# powerbank.net
KiCad netlist of a schematic drawn in EasyEDA Pro
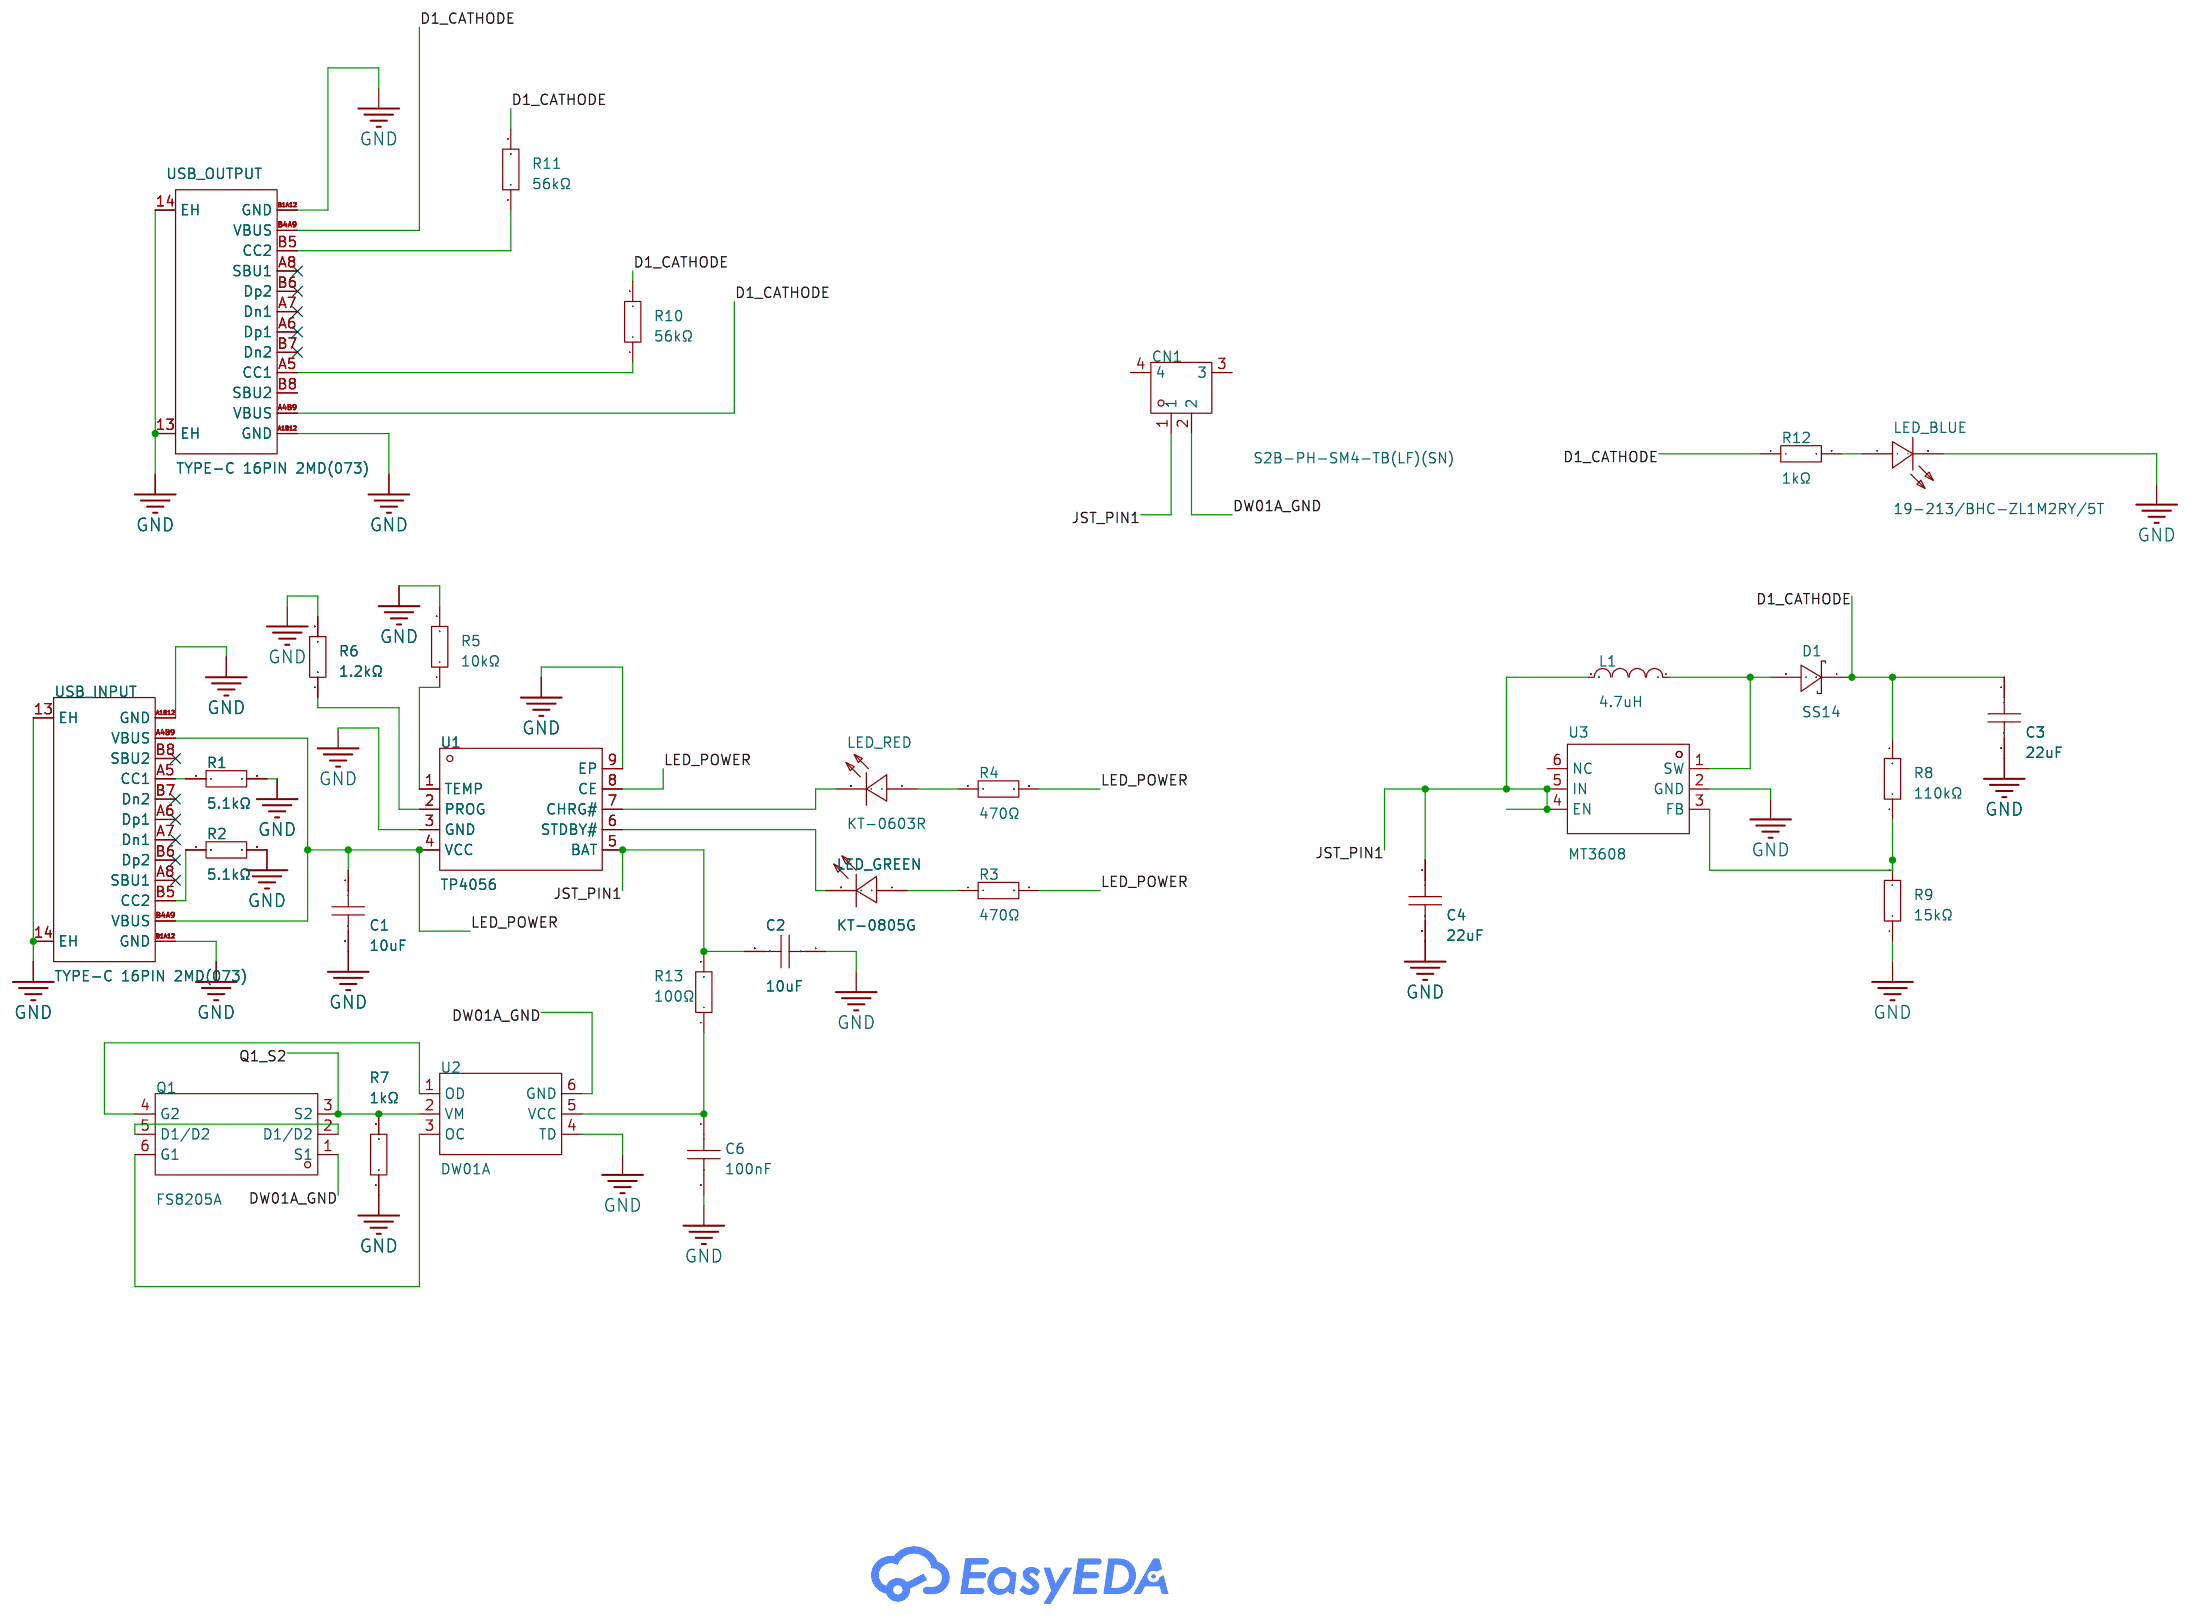
[diagram p0: schematic sheet]

(export (version "E")
  (design (tool "Eeschema 10.0.6"))
  (components
    (comp (ref "C1")
      (value "10uF")
      (footprint "easyedapro:C0201")
      (libsource (lib "easyedapro") (part "CAP"))
    )
    (comp (ref "C2")
      (value "10uF")
      (footprint "easyedapro:C0201")
      (libsource (lib "easyedapro") (part "CAP"))
    )
    (comp (ref "C3")
      (value "22uF")
      (footprint "easyedapro:C0201")
      (libsource (lib "easyedapro") (part "CAP"))
    )
    (comp (ref "C4")
      (value "22uF")
      (footprint "easyedapro:C0201")
      (libsource (lib "easyedapro") (part "CAP"))
    )
    (comp (ref "C6")
      (value "100nF")
      (footprint "easyedapro:C0201")
      (libsource (lib "easyedapro") (part "CAP"))
    )
    (comp (ref "CN1")
      (value "S2B-PH-SM4-TB(LF)(SN)")
      (footprint "easyedapro:CONN-SMD_P2.00_S2B-PH-SM4-TB-LF-SN")
      (fields (field (name "Manufacturer") "JST"))
      (libsource (lib "easyedapro") (part "S2B-PH-SM4-TB(LF)(SN)"))
    )
    (comp (ref "D1")
      (value "SS14")
      (footprint "easyedapro:SMA_L4.2-W2.6-LS5.3-RD")
      (fields (field (name "Manufacturer") "LJ(朗捷)"))
      (libsource (lib "easyedapro") (part "SS14_C7450452"))
    )
    (comp (ref "L1")
      (value "4.7uH")
      (footprint "easyedapro:IND-SMD_L4.4-W4.2")
      (fields (field (name "Manufacturer Part") "FXL0420-4R7-M") (field (name "Manufacturer") "cjiang(长江微电)"))
      (libsource (lib "easyedapro") (part "FXL0420-4R7-M"))
    )
    (comp (ref "LED_BLUE")
      (value "19-213/BHC-ZL1M2RY/5T")
      (footprint "easyedapro:LED0603-R-RD_BLUE")
      (fields (field (name "Manufacturer") "EVERLIGHT(亿光)"))
      (libsource (lib "easyedapro") (part "19-213/BHC-ZL1M2RY/5T"))
    )
    (comp (ref "LED_GREEN")
      (value "KT-0805G")
      (footprint "easyedapro:LED0805-R-RD")
      (fields (field (name "Manufacturer") "KENTO"))
      (libsource (lib "easyedapro") (part "0805G (Green)"))
    )
    (comp (ref "LED_RED")
      (value "KT-0603R")
      (footprint "easyedapro:LED-SMD_L1.6-W0.8-R-RD")
      (fields (field (name "Manufacturer") "KENTO"))
      (libsource (lib "easyedapro") (part "KT-0603R"))
    )
    (comp (ref "Q1")
      (value "FS8205A")
      (footprint "easyedapro:SOT-23-6_L2.9-W1.6-P0.95-LS2.8-BR")
      (fields (field (name "Manufacturer") "TECH PUBLIC(台舟)"))
      (libsource (lib "easyedapro") (part "FS8205A_C2830320"))
    )
    (comp (ref "R1")
      (value "5.1kΩ")
      (footprint "easyedapro:R0603")
      (libsource (lib "easyedapro") (part "Res"))
    )
    (comp (ref "R2")
      (value "5.1kΩ")
      (footprint "easyedapro:R0603")
      (libsource (lib "easyedapro") (part "Res"))
    )
    (comp (ref "R3")
      (value "470Ω")
      (footprint "easyedapro:R0603")
      (libsource (lib "easyedapro") (part "Res"))
    )
    (comp (ref "R4")
      (value "470Ω")
      (footprint "easyedapro:R0603")
      (libsource (lib "easyedapro") (part "Res"))
    )
    (comp (ref "R5")
      (value "10kΩ")
      (footprint "easyedapro:R0603")
      (libsource (lib "easyedapro") (part "Res"))
    )
    (comp (ref "R6")
      (value "1.2kΩ")
      (footprint "easyedapro:R0603")
      (libsource (lib "easyedapro") (part "Res"))
    )
    (comp (ref "R7") (value "1kΩ") (footprint "easyedapro:R0603") (libsource (lib "easyedapro") (part "Res")))
    (comp (ref "R8")
      (value "110kΩ")
      (footprint "easyedapro:R0603")
      (libsource (lib "easyedapro") (part "Res"))
    )
    (comp (ref "R9")
      (value "15kΩ")
      (footprint "easyedapro:R0603")
      (libsource (lib "easyedapro") (part "Res"))
    )
    (comp (ref "R10")
      (value "56kΩ")
      (footprint "easyedapro:R0603")
      (libsource (lib "easyedapro") (part "Res"))
    )
    (comp (ref "R11")
      (value "56kΩ")
      (footprint "easyedapro:R0603")
      (libsource (lib "easyedapro") (part "Res"))
    )
    (comp (ref "R12")
      (value "1kΩ")
      (footprint "easyedapro:R0603")
      (libsource (lib "easyedapro") (part "Res"))
    )
    (comp (ref "R13")
      (value "100Ω")
      (footprint "easyedapro:R0603")
      (libsource (lib "easyedapro") (part "Res"))
    )
    (comp (ref "U1")
      (value "TP4056")
      (footprint "easyedapro:ESOP-8_L4.9-W3.9-P1.27-LS6.0-BL-EP")
      (fields (field (name "Manufacturer") "TPOWER(天源)"))
      (libsource (lib "easyedapro") (part "TP4056_C382139"))
    )
    (comp (ref "U2")
      (value "DW01A")
      (footprint "easyedapro:SOT-23-6_L2.9-W1.6-P0.95-LS2.8-BL")
      (fields (field (name "Manufacturer") "PUOLOP(迪浦)"))
      (libsource (lib "easyedapro") (part "DW01A_C351410"))
    )
    (comp (ref "U3")
      (value "MT3608")
      (footprint "easyedapro:SOT-23-6_L2.9-W1.6-P0.95-LS2.8-BL")
      (fields (field (name "Manufacturer") "西安航天民芯"))
      (libsource (lib "easyedapro") (part "MT3608"))
    )
    (comp (ref "USB_INPUT")
      (value "TYPE-C 16PIN 2MD(073)")
      (footprint "easyedapro:USB-C-SMD_TYPE-C-16PIN-2MD-073")
      (fields (field (name "Manufacturer") "SHOU HAN(首韩)"))
      (libsource (lib "easyedapro") (part "TYPE-C 16PIN 2MD(073)"))
    )
    (comp (ref "USB_OUTPUT")
      (value "TYPE-C 16PIN 2MD(073)")
      (footprint "easyedapro:USB-C-SMD_TYPE-C-16PIN-2MD-073")
      (fields (field (name "Manufacturer") "SHOU HAN(首韩)"))
      (libsource (lib "easyedapro") (part "TYPE-C 16PIN 2MD(073)"))
    )
  )
  (nets
    (net (code "1") (name "/D1_CATHODE") (class "Default")
      (node (ref "C3") (pin "1") (pinfunction "1_1") (pintype "input"))
      (node (ref "D1") (pin "1") (pinfunction "C_1") (pintype "unspecified"))
      (node (ref "R10") (pin "2") (pinfunction "2_2") (pintype "input"))
      (node (ref "R11") (pin "2") (pinfunction "2_2") (pintype "input"))
      (node (ref "R12") (pin "1") (pinfunction "1_1") (pintype "input"))
      (node (ref "R8") (pin "2") (pinfunction "2_2") (pintype "input"))
      (node (ref "USB_OUTPUT") (pin "A4B9") (pinfunction "VBUS_A4B9") (pintype "unspecified"))
      (node (ref "USB_OUTPUT") (pin "B4A9") (pinfunction "VBUS_B4A9") (pintype "unspecified"))
    )
    (net (code "2") (name "/DW01A_GND") (class "Default")
      (node (ref "CN1") (pin "2") (pinfunction "2_2") (pintype "unspecified"))
      (node (ref "Q1") (pin "1") (pinfunction "S1_1") (pintype "unspecified"))
      (node (ref "U2") (pin "6") (pinfunction "GND_6") (pintype "unspecified"))
    )
    (net (code "3") (name "/JST_PIN1") (class "Default")
      (node (ref "C2") (pin "2") (pinfunction "2_2") (pintype "input"))
      (node (ref "C4") (pin "1") (pinfunction "1_1") (pintype "input"))
      (node (ref "CN1") (pin "1") (pinfunction "1_1") (pintype "unspecified"))
      (node (ref "L1") (pin "2") (pinfunction "2_2") (pintype "unspecified"))
      (node (ref "R13") (pin "2") (pinfunction "2_2") (pintype "input"))
      (node (ref "U1") (pin "5") (pinfunction "BAT_5") (pintype "unspecified"))
      (node (ref "U3") (pin "4") (pinfunction "EN_4") (pintype "unspecified"))
      (node (ref "U3") (pin "5") (pinfunction "IN_5") (pintype "unspecified"))
    )
    (net (code "4") (name "/LED_POWER") (class "Default")
      (node (ref "C1") (pin "1") (pinfunction "1_1") (pintype "input"))
      (node (ref "R3") (pin "2") (pinfunction "2_2") (pintype "input"))
      (node (ref "R4") (pin "2") (pinfunction "2_2") (pintype "input"))
      (node (ref "U1") (pin "4") (pinfunction "VCC_4") (pintype "unspecified"))
      (node (ref "U1") (pin "8") (pinfunction "CE_8") (pintype "unspecified"))
      (node (ref "USB_INPUT") (pin "A4B9") (pinfunction "VBUS_A4B9") (pintype "unspecified"))
      (node (ref "USB_INPUT") (pin "B4A9") (pinfunction "VBUS_B4A9") (pintype "unspecified"))
    )
    (net (code "5") (name "/Q1_S2") (class "Default")
      (node (ref "Q1") (pin "3") (pinfunction "S2_3") (pintype "unspecified"))
      (node (ref "R7") (pin "2") (pinfunction "2_2") (pintype "input"))
      (node (ref "U2") (pin "2") (pinfunction "VM_2") (pintype "unspecified"))
    )
    (net (code "6") (name "GND") (class "Default")
      (node (ref "C1") (pin "2") (pinfunction "2_2") (pintype "input"))
      (node (ref "C2") (pin "1") (pinfunction "1_1") (pintype "input"))
      (node (ref "C3") (pin "2") (pinfunction "2_2") (pintype "input"))
      (node (ref "C4") (pin "2") (pinfunction "2_2") (pintype "input"))
      (node (ref "C6") (pin "2") (pinfunction "2_2") (pintype "input"))
      (node (ref "LED_BLUE") (pin "2") (pinfunction "-_2") (pintype "unspecified"))
      (node (ref "R1") (pin "2") (pinfunction "2_2") (pintype "input"))
      (node (ref "R2") (pin "2") (pinfunction "2_2") (pintype "input"))
      (node (ref "R5") (pin "2") (pinfunction "2_2") (pintype "input"))
      (node (ref "R6") (pin "2") (pinfunction "2_2") (pintype "input"))
      (node (ref "R7") (pin "1") (pinfunction "1_1") (pintype "input"))
      (node (ref "R9") (pin "1") (pinfunction "1_1") (pintype "input"))
      (node (ref "U1") (pin "3") (pinfunction "GND_3") (pintype "unspecified"))
      (node (ref "U1") (pin "9") (pinfunction "EP_9") (pintype "unspecified"))
      (node (ref "U2") (pin "4") (pinfunction "TD_4") (pintype "unspecified"))
      (node (ref "U3") (pin "2") (pinfunction "GND_2") (pintype "unspecified"))
      (node (ref "USB_INPUT") (pin "13") (pinfunction "EH_13") (pintype "unspecified"))
      (node (ref "USB_INPUT") (pin "14") (pinfunction "EH_14") (pintype "unspecified"))
      (node (ref "USB_INPUT") (pin "A1B12") (pinfunction "GND_A1B12") (pintype "unspecified"))
      (node (ref "USB_INPUT") (pin "B1A12") (pinfunction "GND_B1A12") (pintype "unspecified"))
      (node (ref "USB_OUTPUT") (pin "13") (pinfunction "EH_13") (pintype "unspecified"))
      (node (ref "USB_OUTPUT") (pin "14") (pinfunction "EH_14") (pintype "unspecified"))
      (node (ref "USB_OUTPUT") (pin "A1B12") (pinfunction "GND_A1B12") (pintype "unspecified"))
      (node (ref "USB_OUTPUT") (pin "B1A12") (pinfunction "GND_B1A12") (pintype "unspecified"))
    )
    (net (code "7") (name "Net-(D1-A)") (class "Default")
      (node (ref "D1") (pin "2") (pinfunction "A_2") (pintype "unspecified"))
      (node (ref "L1") (pin "1") (pinfunction "1_1") (pintype "unspecified"))
      (node (ref "U3") (pin "1") (pinfunction "SW_1") (pintype "unspecified"))
    )
    (net (code "8") (name "Net-(LED_BLUE-+)") (class "Default")
      (node (ref "LED_BLUE") (pin "1") (pinfunction "+_1") (pintype "unspecified"))
      (node (ref "R12") (pin "2") (pinfunction "2_2") (pintype "input"))
    )
    (net (code "9") (name "Net-(LED_GREEN-A)") (class "Default")
      (node (ref "LED_GREEN") (pin "1") (pinfunction "A_1") (pintype "unspecified"))
      (node (ref "R3") (pin "1") (pinfunction "1_1") (pintype "input"))
    )
    (net (code "10") (name "Net-(LED_GREEN-K)") (class "Default")
      (node (ref "LED_GREEN") (pin "2") (pinfunction "K_2") (pintype "unspecified"))
      (node (ref "U1") (pin "6") (pinfunction "STDBY#_6") (pintype "unspecified"))
    )
    (net (code "11") (name "Net-(LED_RED-A)") (class "Default")
      (node (ref "LED_RED") (pin "1") (pinfunction "A_1") (pintype "unspecified"))
      (node (ref "R4") (pin "1") (pinfunction "1_1") (pintype "input"))
    )
    (net (code "12") (name "Net-(LED_RED-K)") (class "Default")
      (node (ref "LED_RED") (pin "2") (pinfunction "K_2") (pintype "unspecified"))
      (node (ref "U1") (pin "7") (pinfunction "CHRG#_7") (pintype "unspecified"))
    )
    (net (code "13") (name "Net-(Q1-D1{slash}D2-Pad2)") (class "Default")
      (node (ref "Q1") (pin "2") (pinfunction "D1/D2_2") (pintype "unspecified"))
      (node (ref "Q1") (pin "5") (pinfunction "D1/D2_5") (pintype "unspecified"))
    )
    (net (code "14") (name "Net-(Q1-G1)") (class "Default")
      (node (ref "Q1") (pin "6") (pinfunction "G1_6") (pintype "unspecified"))
      (node (ref "U2") (pin "3") (pinfunction "OC_3") (pintype "unspecified"))
    )
    (net (code "15") (name "Net-(Q1-G2)") (class "Default")
      (node (ref "Q1") (pin "4") (pinfunction "G2_4") (pintype "unspecified"))
      (node (ref "U2") (pin "1") (pinfunction "OD_1") (pintype "unspecified"))
    )
    (net (code "16") (name "Net-(U1-PROG)") (class "Default")
      (node (ref "R6") (pin "1") (pinfunction "1_1") (pintype "input"))
      (node (ref "U1") (pin "2") (pinfunction "PROG_2") (pintype "unspecified"))
    )
    (net (code "17") (name "Net-(U1-TEMP)") (class "Default")
      (node (ref "R5") (pin "1") (pinfunction "1_1") (pintype "input"))
      (node (ref "U1") (pin "1") (pinfunction "TEMP_1") (pintype "unspecified"))
    )
    (net (code "18") (name "Net-(U2-VCC)") (class "Default")
      (node (ref "C6") (pin "1") (pinfunction "1_1") (pintype "input"))
      (node (ref "R13") (pin "1") (pinfunction "1_1") (pintype "input"))
      (node (ref "U2") (pin "5") (pinfunction "VCC_5") (pintype "unspecified"))
    )
    (net (code "19") (name "Net-(U3-FB)") (class "Default")
      (node (ref "R8") (pin "1") (pinfunction "1_1") (pintype "input"))
      (node (ref "R9") (pin "2") (pinfunction "2_2") (pintype "input"))
      (node (ref "U3") (pin "3") (pinfunction "FB_3") (pintype "unspecified"))
    )
    (net (code "20") (name "Net-(USB_INPUT-CC1)") (class "Default")
      (node (ref "R1") (pin "1") (pinfunction "1_1") (pintype "input"))
      (node (ref "USB_INPUT") (pin "A5") (pinfunction "CC1_A5") (pintype "unspecified"))
    )
    (net (code "21") (name "Net-(USB_INPUT-CC2)") (class "Default")
      (node (ref "R2") (pin "1") (pinfunction "1_1") (pintype "input"))
      (node (ref "USB_INPUT") (pin "B5") (pinfunction "CC2_B5") (pintype "unspecified"))
    )
    (net (code "22") (name "Net-(USB_OUTPUT-CC1)") (class "Default")
      (node (ref "R10") (pin "1") (pinfunction "1_1") (pintype "input"))
      (node (ref "USB_OUTPUT") (pin "A5") (pinfunction "CC1_A5") (pintype "unspecified"))
    )
    (net (code "23") (name "Net-(USB_OUTPUT-CC2)") (class "Default")
      (node (ref "R11") (pin "1") (pinfunction "1_1") (pintype "input"))
      (node (ref "USB_OUTPUT") (pin "B5") (pinfunction "CC2_B5") (pintype "unspecified"))
    )
    (net (code "24") (name "unconnected-(CN1-Pad3)") (class "Default")
      (node (ref "CN1") (pin "3") (pinfunction "3_3") (pintype "unspecified"))
    )
    (net (code "25") (name "unconnected-(CN1-Pad4)") (class "Default")
      (node (ref "CN1") (pin "4") (pinfunction "4_4") (pintype "unspecified"))
    )
    (net (code "26") (name "unconnected-(U3-NC-Pad6)") (class "Default")
      (node (ref "U3") (pin "6") (pinfunction "NC_6") (pintype "unspecified"))
    )
    (net (code "27") (name "unconnected-(USB_INPUT-Dn1-PadA7)") (class "Default")
      (node (ref "USB_INPUT") (pin "A7") (pinfunction "Dn1_A7") (pintype "unspecified+no_connect"))
    )
    (net (code "28") (name "unconnected-(USB_INPUT-Dn2-PadB7)") (class "Default")
      (node (ref "USB_INPUT") (pin "B7") (pinfunction "Dn2_B7") (pintype "unspecified+no_connect"))
    )
    (net (code "29") (name "unconnected-(USB_INPUT-Dp1-PadA6)") (class "Default")
      (node (ref "USB_INPUT") (pin "A6") (pinfunction "Dp1_A6") (pintype "unspecified+no_connect"))
    )
    (net (code "30") (name "unconnected-(USB_INPUT-Dp2-PadB6)") (class "Default")
      (node (ref "USB_INPUT") (pin "B6") (pinfunction "Dp2_B6") (pintype "unspecified+no_connect"))
    )
    (net (code "31") (name "unconnected-(USB_INPUT-SBU1-PadA8)") (class "Default")
      (node (ref "USB_INPUT") (pin "A8") (pinfunction "SBU1_A8") (pintype "unspecified+no_connect"))
    )
    (net (code "32") (name "unconnected-(USB_INPUT-SBU2-PadB8)") (class "Default")
      (node (ref "USB_INPUT") (pin "B8") (pinfunction "SBU2_B8") (pintype "unspecified+no_connect"))
    )
    (net (code "33") (name "unconnected-(USB_OUTPUT-Dn1-PadA7)") (class "Default")
      (node (ref "USB_OUTPUT") (pin "A7") (pinfunction "Dn1_A7") (pintype "unspecified+no_connect"))
    )
    (net (code "34") (name "unconnected-(USB_OUTPUT-Dn2-PadB7)") (class "Default")
      (node (ref "USB_OUTPUT") (pin "B7") (pinfunction "Dn2_B7") (pintype "unspecified+no_connect"))
    )
    (net (code "35") (name "unconnected-(USB_OUTPUT-Dp1-PadA6)") (class "Default")
      (node (ref "USB_OUTPUT") (pin "A6") (pinfunction "Dp1_A6") (pintype "unspecified+no_connect"))
    )
    (net (code "36") (name "unconnected-(USB_OUTPUT-Dp2-PadB6)") (class "Default")
      (node (ref "USB_OUTPUT") (pin "B6") (pinfunction "Dp2_B6") (pintype "unspecified+no_connect"))
    )
    (net (code "37") (name "unconnected-(USB_OUTPUT-SBU1-PadA8)") (class "Default")
      (node (ref "USB_OUTPUT") (pin "A8") (pinfunction "SBU1_A8") (pintype "unspecified+no_connect"))
    )
    (net (code "38") (name "unconnected-(USB_OUTPUT-SBU2-PadB8)") (class "Default")
      (node (ref "USB_OUTPUT") (pin "B8") (pinfunction "SBU2_B8") (pintype "unspecified"))
    )
  )
)
